# maskPlanC-PCB0.net
KiCad netlist of a schematic drawn in EAGLE
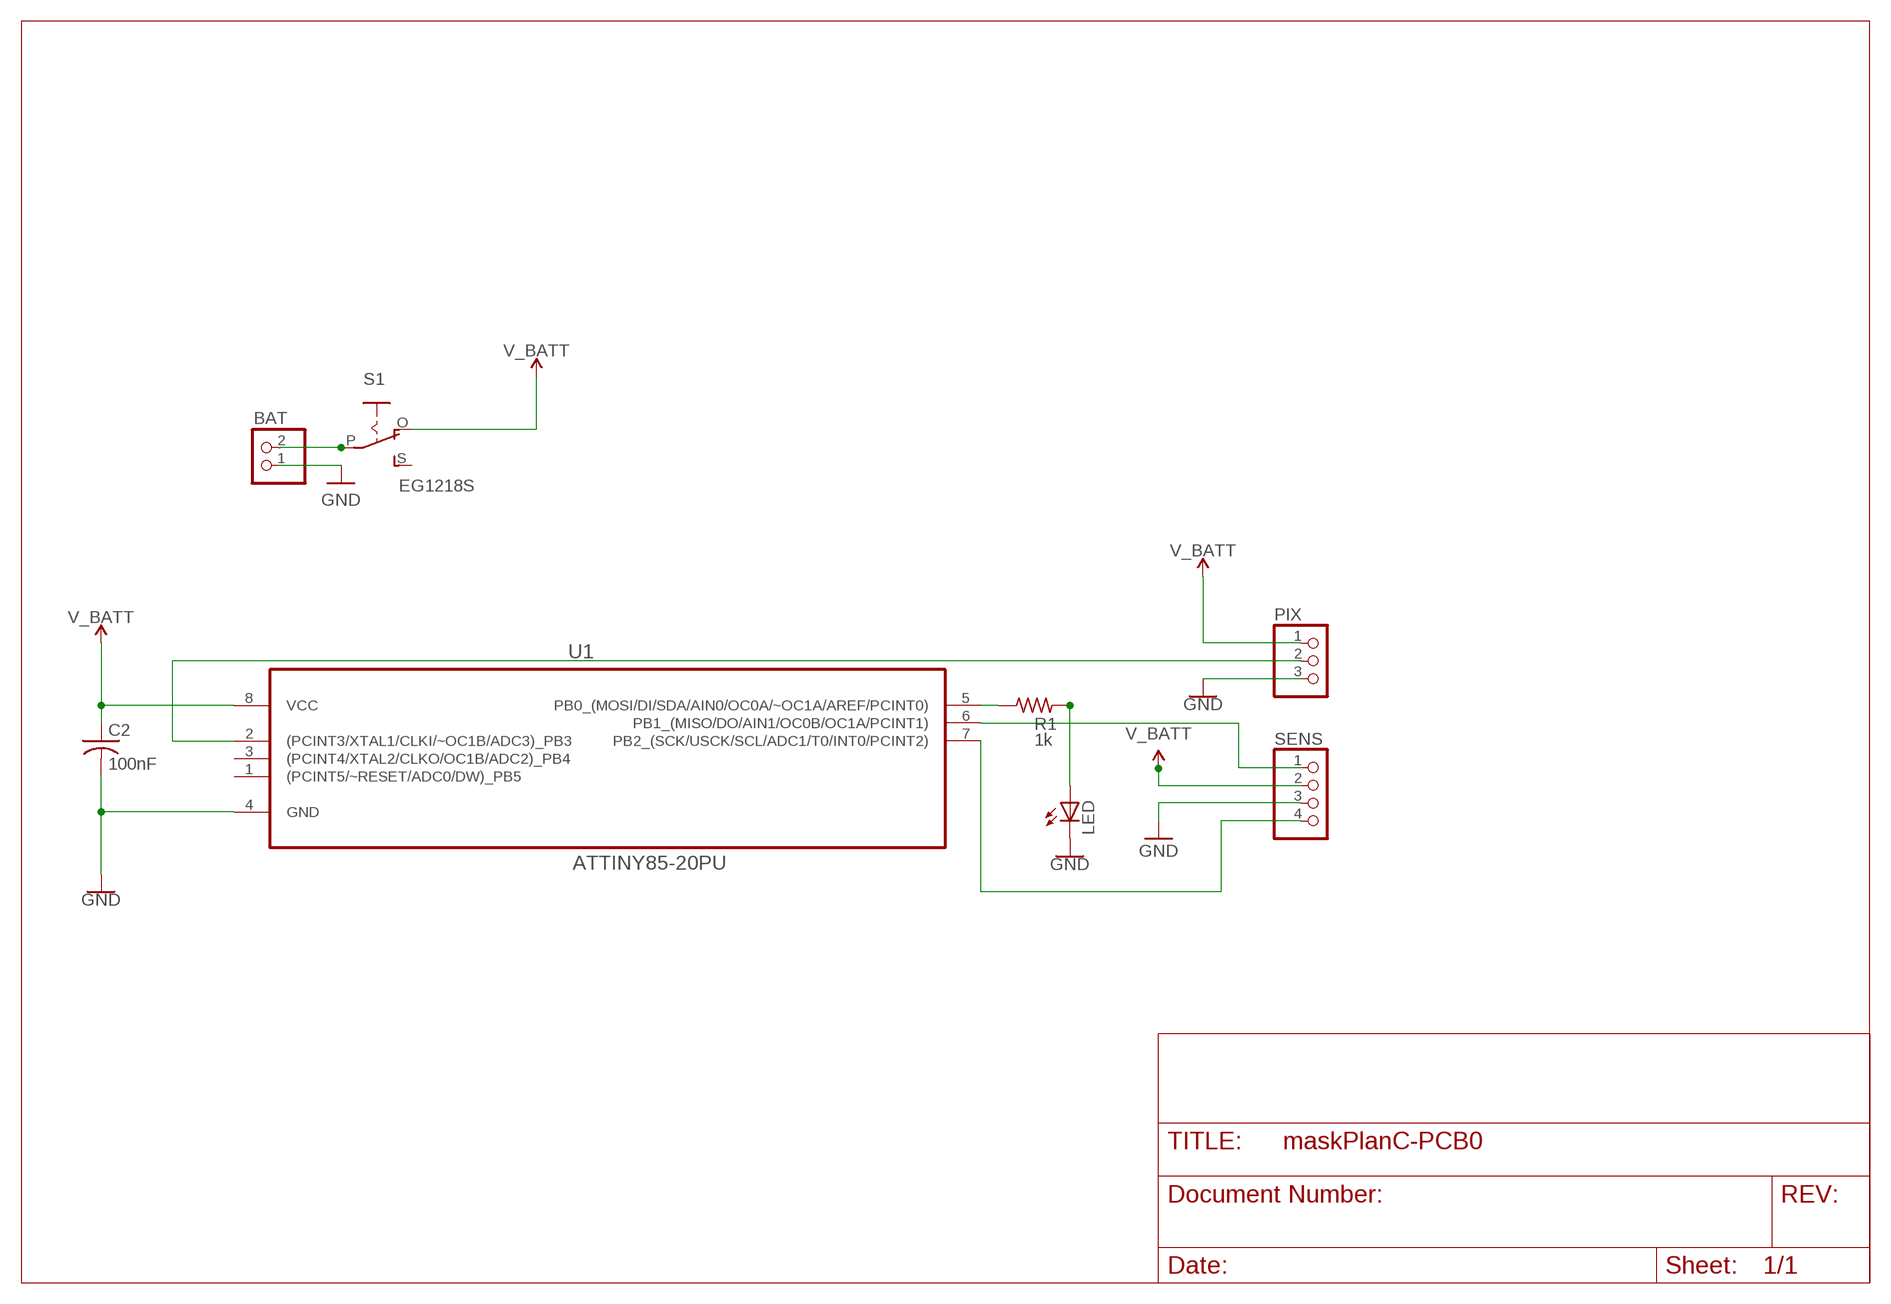
[diagram p0: schematic, sheet 1]

(export (version "E")
  (design (tool "Eeschema 10.0.6"))
  (components
    (comp (ref "BAT")
      (value "PINHD-1X2")
      (footprint "eagle-import:1X02")
      (libsource (lib "eagle-import") (part "PINHD-1X2"))
    )
    (comp (ref "C2")
      (value "100nF")
      (footprint "eagle-import:C050-025X075")
      (libsource (lib "eagle-import") (part "C-US050-025X075"))
    )
    (comp (ref "LED")
      (value "LED5MM")
      (footprint "eagle-import:LED5MM")
      (libsource (lib "eagle-import") (part "LED5MM"))
    )
    (comp (ref "PIX")
      (value "PINHD-1X3")
      (footprint "eagle-import:1X03")
      (libsource (lib "eagle-import") (part "PINHD-1X3"))
    )
    (comp (ref "R1")
      (value "1k")
      (footprint "eagle-import:0204_7")
      (libsource (lib "eagle-import") (part "R-US_0204/7"))
    )
    (comp (ref "S1")
      (value "EG1218S")
      (footprint "eagle-import:EG1218")
      (fields (field (name "MF") "E-Switch") (field (name "MP") "EG1218"))
      (libsource (lib "eagle-import") (part "EG1218S"))
    )
    (comp (ref "SENS")
      (value "PINHD-1X4")
      (footprint "eagle-import:1X04")
      (libsource (lib "eagle-import") (part "PINHD-1X4"))
    )
    (comp (ref "U1")
      (value "ATTINY85-20PU")
      (footprint "eagle-import:DIP254P762X533-8")
      (fields (field (name "MF") "Microchip"))
      (libsource (lib "eagle-import") (part "ATTINY85-20PU"))
    )
  )
  (nets
    (net (code "1") (name "GND") (class "Default")
      (node (ref "BAT") (pin "1") (pinfunction "1_1") (pintype "passive"))
      (node (ref "C2") (pin "2") (pinfunction "2_2") (pintype "passive"))
      (node (ref "LED") (pin "K") (pinfunction "C_K") (pintype "passive"))
      (node (ref "PIX") (pin "3") (pinfunction "3_3") (pintype "passive"))
      (node (ref "SENS") (pin "3") (pinfunction "3_3") (pintype "passive"))
      (node (ref "U1") (pin "4") (pinfunction "GND_4") (pintype "passive"))
    )
    (net (code "2") (name "Net-(BAT-Pad2)") (class "Default")
      (node (ref "BAT") (pin "2") (pinfunction "2_2") (pintype "passive"))
      (node (ref "S1") (pin "P") (pinfunction "P_P") (pintype "passive"))
    )
    (net (code "3") (name "Net-(LED-PadA)") (class "Default")
      (node (ref "LED") (pin "A") (pinfunction "A_A") (pintype "passive"))
      (node (ref "R1") (pin "2") (pinfunction "2_2") (pintype "passive"))
    )
    (net (code "4") (name "Net-(U1-(PCINT3{slash}XTAL1{slash}CLKI{slash}~{OC1B{slash}ADC3})_PB3)") (class "Default")
      (node (ref "PIX") (pin "2") (pinfunction "2_2") (pintype "passive"))
      (node (ref "U1") (pin "2") (pinfunction "(PCINT3/XTAL1/CLKI/~{OC1B/ADC3})_PB3_2") (pintype "bidirectional"))
    )
    (net (code "5") (name "Net-(U1-PB0_(MOSI{slash}DI{slash}SDA{slash}AIN0{slash}OC0A{slash}~{OC1A{slash}AREF{slash}PCINT0}))") (class "Default")
      (node (ref "R1") (pin "1") (pinfunction "1_1") (pintype "passive"))
      (node (ref "U1") (pin "5") (pinfunction "PB0_(MOSI/DI/SDA/AIN0/OC0A/~{OC1A/AREF/PCINT0})_5") (pintype "bidirectional"))
    )
    (net (code "6") (name "Net-(U1-PB1_(MISO{slash}DO{slash}AIN1{slash}OC0B{slash}OC1A{slash}PCINT1))") (class "Default")
      (node (ref "SENS") (pin "1") (pinfunction "1_1") (pintype "passive"))
      (node (ref "U1") (pin "6") (pinfunction "PB1_(MISO/DO/AIN1/OC0B/OC1A/PCINT1)_6") (pintype "bidirectional"))
    )
    (net (code "7") (name "Net-(U1-PB2_(SCK{slash}USCK{slash}SCL{slash}ADC1{slash}T0{slash}INT0{slash}PCINT2))") (class "Default")
      (node (ref "SENS") (pin "4") (pinfunction "4_4") (pintype "passive"))
      (node (ref "U1") (pin "7") (pinfunction "PB2_(SCK/USCK/SCL/ADC1/T0/INT0/PCINT2)_7") (pintype "bidirectional"))
    )
    (net (code "8") (name "V_BATT") (class "Default")
      (node (ref "C2") (pin "1") (pinfunction "1_1") (pintype "passive"))
      (node (ref "PIX") (pin "1") (pinfunction "1_1") (pintype "passive"))
      (node (ref "S1") (pin "O") (pinfunction "O_O") (pintype "passive"))
      (node (ref "SENS") (pin "2") (pinfunction "2_2") (pintype "passive"))
      (node (ref "U1") (pin "8") (pinfunction "VCC_8") (pintype "power_in"))
    )
    (net (code "9") (name "unconnected-(S1-PadS)") (class "Default")
      (node (ref "S1") (pin "S") (pinfunction "S_S") (pintype "passive"))
    )
    (net (code "10") (name "unconnected-(U1-(PCINT4{slash}XTAL2{slash}CLKO{slash}OC1B{slash}ADC2)_PB4-Pad3)") (class "Default")
      (node (ref "U1") (pin "3") (pinfunction "(PCINT4/XTAL2/CLKO/OC1B/ADC2)_PB4_3") (pintype "bidirectional"))
    )
    (net (code "11") (name "unconnected-(U1-(PCINT5{slash}~{RESET{slash}ADC0{slash}DW})_PB5-Pad1)") (class "Default")
      (node (ref "U1") (pin "1") (pinfunction "(PCINT5/~{RESET/ADC0/DW})_PB5_1") (pintype "bidirectional"))
    )
  )
)
